# EDU_High-Speed-Design_CPU_DDR3.net
KiCad netlist of a schematic drawn in Altium Designer
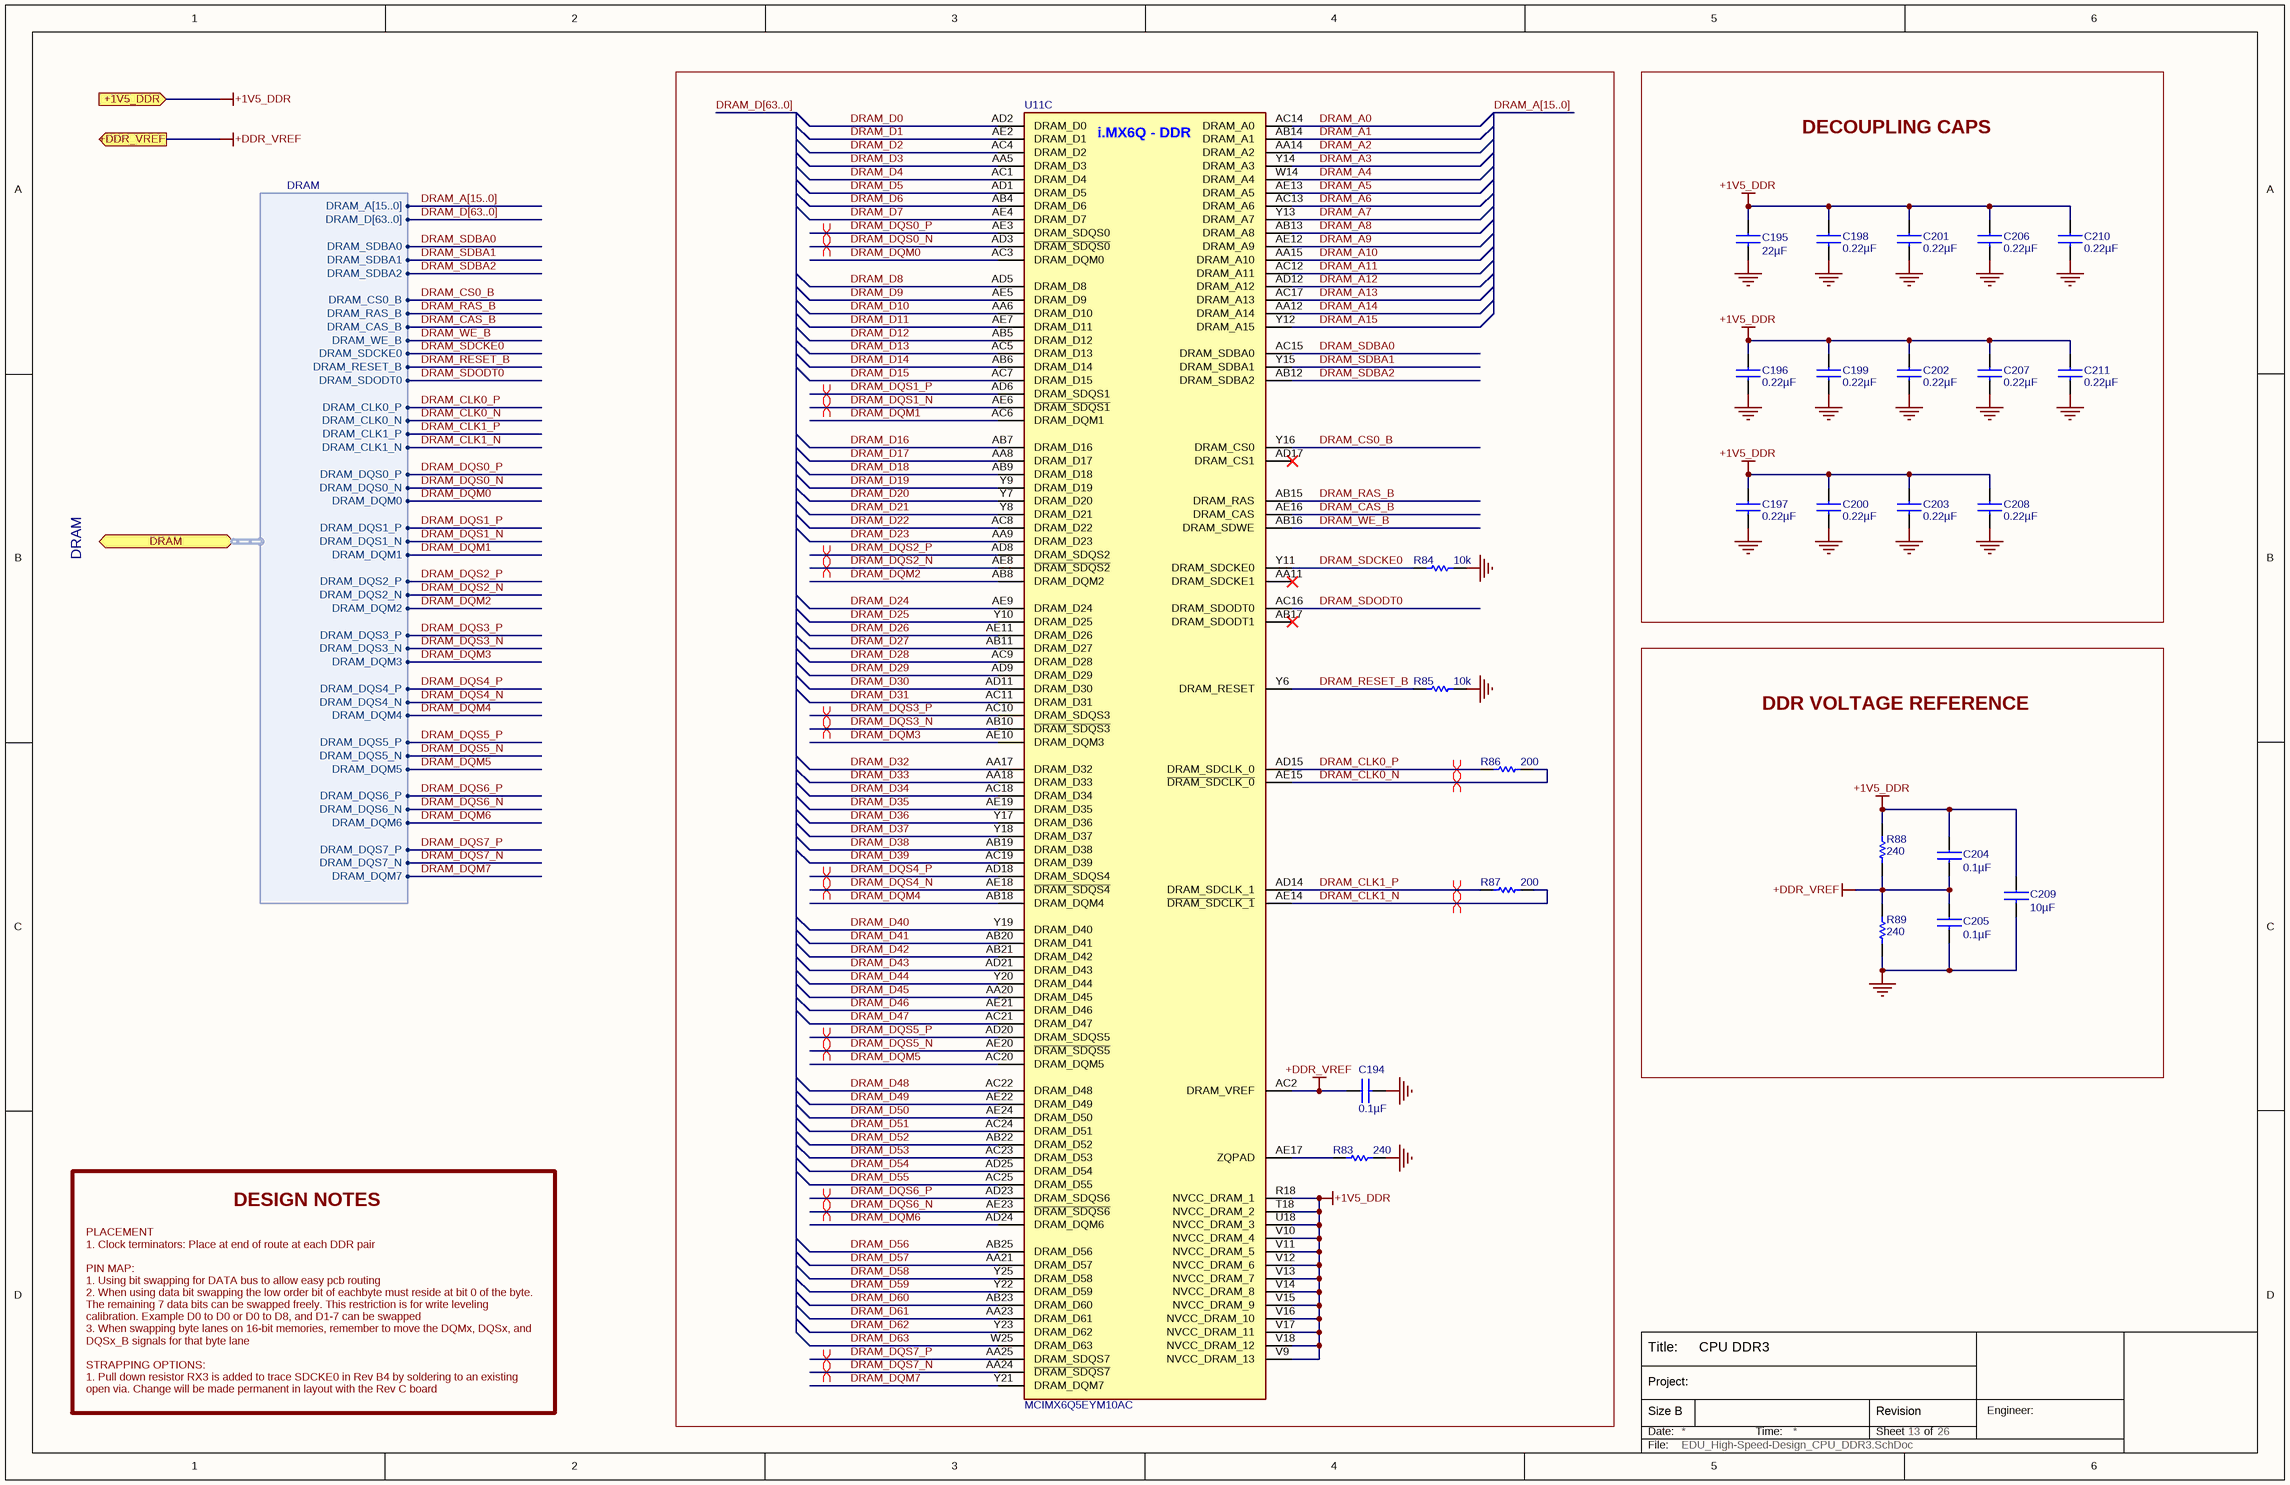
[diagram p0: EDU_High-Speed-Design_CPU_DDR3.SchDoc]

(export (version "E")
  (design (tool "Eeschema 10.0.6"))
  (components
    (comp (ref "C194")
      (value "0.1µF")
      (footprint "C0402")
      (description "CAP CER .10UF 50V X5R 10% 0402")
      (fields (field (name "VOLTAGE") "50V"))
      (libsource (lib "EDU_High-Speed-Design") (part "C1005X5R1H104K"))
    )
    (comp (ref "C195")
      (value "22µF")
      (footprint "C0603")
      (description "CAP CER 22UF 4V 20% X5R 0603")
      (fields (field (name "VOLTAGE") "4V"))
      (libsource (lib "EDU_High-Speed-Design") (part "GRM188R60G226MEA0L"))
    )
    (comp (ref "C196")
      (value "0.22µF")
      (footprint "C0402")
      (description "CAP CER .22UF 25V X5R 20% 0402")
      (fields (field (name "VOLTAGE") "25V"))
      (libsource (lib "EDU_High-Speed-Design") (part "C1005X5R1E224M"))
    )
    (comp (ref "C197")
      (value "0.22µF")
      (footprint "C0402")
      (description "CAP CER .22UF 25V X5R 20% 0402")
      (fields (field (name "VOLTAGE") "25V"))
      (libsource (lib "EDU_High-Speed-Design") (part "C1005X5R1E224M"))
    )
    (comp (ref "C198")
      (value "0.22µF")
      (footprint "C0402")
      (description "CAP CER .22UF 25V X5R 20% 0402")
      (fields (field (name "VOLTAGE") "25V"))
      (libsource (lib "EDU_High-Speed-Design") (part "C1005X5R1E224M"))
    )
    (comp (ref "C199")
      (value "0.22µF")
      (footprint "C0402")
      (description "CAP CER .22UF 25V X5R 20% 0402")
      (fields (field (name "VOLTAGE") "25V"))
      (libsource (lib "EDU_High-Speed-Design") (part "C1005X5R1E224M"))
    )
    (comp (ref "C200")
      (value "0.22µF")
      (footprint "C0402")
      (description "CAP CER .22UF 25V X5R 20% 0402")
      (fields (field (name "VOLTAGE") "25V"))
      (libsource (lib "EDU_High-Speed-Design") (part "C1005X5R1E224M"))
    )
    (comp (ref "C201")
      (value "0.22µF")
      (footprint "C0402")
      (description "CAP CER .22UF 25V X5R 20% 0402")
      (fields (field (name "VOLTAGE") "25V"))
      (libsource (lib "EDU_High-Speed-Design") (part "C1005X5R1E224M"))
    )
    (comp (ref "C202")
      (value "0.22µF")
      (footprint "C0402")
      (description "CAP CER .22UF 25V X5R 20% 0402")
      (fields (field (name "VOLTAGE") "25V"))
      (libsource (lib "EDU_High-Speed-Design") (part "C1005X5R1E224M"))
    )
    (comp (ref "C203")
      (value "0.22µF")
      (footprint "C0402")
      (description "CAP CER .22UF 25V X5R 20% 0402")
      (fields (field (name "VOLTAGE") "25V"))
      (libsource (lib "EDU_High-Speed-Design") (part "C1005X5R1E224M"))
    )
    (comp (ref "C204")
      (value "0.1µF")
      (footprint "C0402")
      (description "CAP CER .10UF 50V X5R 10% 0402")
      (fields (field (name "VOLTAGE") "50V"))
      (libsource (lib "EDU_High-Speed-Design") (part "C1005X5R1H104K"))
    )
    (comp (ref "C205")
      (value "0.1µF")
      (footprint "C0402")
      (description "CAP CER .10UF 50V X5R 10% 0402")
      (fields (field (name "VOLTAGE") "50V"))
      (libsource (lib "EDU_High-Speed-Design") (part "C1005X5R1H104K"))
    )
    (comp (ref "C206")
      (value "0.22µF")
      (footprint "C0402")
      (description "CAP CER .22UF 25V X5R 20% 0402")
      (fields (field (name "VOLTAGE") "25V"))
      (libsource (lib "EDU_High-Speed-Design") (part "C1005X5R1E224M"))
    )
    (comp (ref "C207")
      (value "0.22µF")
      (footprint "C0402")
      (description "CAP CER .22UF 25V X5R 20% 0402")
      (fields (field (name "VOLTAGE") "25V"))
      (libsource (lib "EDU_High-Speed-Design") (part "C1005X5R1E224M"))
    )
    (comp (ref "C208")
      (value "0.22µF")
      (footprint "C0402")
      (description "CAP CER .22UF 25V X5R 20% 0402")
      (fields (field (name "VOLTAGE") "25V"))
      (libsource (lib "EDU_High-Speed-Design") (part "C1005X5R1E224M"))
    )
    (comp (ref "C209")
      (value "10µF")
      (footprint "C0603")
      (description "CAP CER 10UF 6.3V X5R 20% 0603")
      (fields (field (name "VOLTAGE") "6.3V"))
      (libsource (lib "EDU_High-Speed-Design") (part "C1608X5R0J106M"))
    )
    (comp (ref "C210")
      (value "0.22µF")
      (footprint "C0402")
      (description "CAP CER .22UF 25V X5R 20% 0402")
      (fields (field (name "VOLTAGE") "25V"))
      (libsource (lib "EDU_High-Speed-Design") (part "C1005X5R1E224M"))
    )
    (comp (ref "C211")
      (value "0.22µF")
      (footprint "C0402")
      (description "CAP CER .22UF 25V X5R 20% 0402")
      (fields (field (name "VOLTAGE") "25V"))
      (libsource (lib "EDU_High-Speed-Design") (part "C1005X5R1E224M"))
    )
    (comp (ref "R83")
      (value "240")
      (footprint "R0402")
      (description "RES TF 240 OHM 1% 0.0625W 0402")
      (libsource (lib "EDU_High-Speed-Design") (part "RMCF0402FT240R"))
    )
    (comp (ref "R84")
      (value "10k")
      (footprint "R0402")
      (description "RES 10.0K OHM 1/16W 1% 0402 SMD")
      (libsource (lib "EDU_High-Speed-Design") (part "RC0402FR-0710KL"))
    )
    (comp (ref "R85")
      (value "10k")
      (footprint "R0402")
      (description "RES 10.0K OHM 1/16W 1% 0402 SMD")
      (libsource (lib "EDU_High-Speed-Design") (part "RC0402FR-0710KL"))
    )
    (comp (ref "R86")
      (value "200")
      (footprint "R0402")
      (description "RES 200 OHM 1/16W 1% 0402 SMD")
      (libsource (lib "EDU_High-Speed-Design") (part "CRCW0402200RFKED"))
    )
    (comp (ref "R87")
      (value "200")
      (footprint "R0402")
      (description "RES 200 OHM 1/16W 1% 0402 SMD")
      (libsource (lib "EDU_High-Speed-Design") (part "CRCW0402200RFKED"))
    )
    (comp (ref "R88")
      (value "240")
      (footprint "R0402")
      (description "RES TF 240 OHM 1% 0.0625W 0402")
      (libsource (lib "EDU_High-Speed-Design") (part "RMCF0402FT240R"))
    )
    (comp (ref "R89")
      (value "240")
      (footprint "R0402")
      (description "RES TF 240 OHM 1% 0.0625W 0402")
      (libsource (lib "EDU_High-Speed-Design") (part "RMCF0402FT240R"))
    )
    (comp (ref "U11")
      (value "MCIMX6Q5EYM10AC")
      (footprint "MCIMX6Q5EYM10AC")
      (description "IC MCU 32BIT ARM QUAD 624FCBGA")
      (libsource (lib "EDU_High-Speed-Design") (part "MCIMX6Q5EYM10AC"))
    )
  )
  (nets
    (net (code "2") (name "+1V5_DDR") (class "Default")
      (node (ref "C195") (pin "1") (pinfunction "1_1") (pintype "passive"))
      (node (ref "C196") (pin "1") (pinfunction "1_1") (pintype "passive"))
      (node (ref "C197") (pin "1") (pinfunction "1_1") (pintype "passive"))
      (node (ref "C198") (pin "1") (pinfunction "1_1") (pintype "passive"))
      (node (ref "C199") (pin "1") (pinfunction "1_1") (pintype "passive"))
      (node (ref "C200") (pin "1") (pinfunction "1_1") (pintype "passive"))
      (node (ref "C201") (pin "1") (pinfunction "1_1") (pintype "passive"))
      (node (ref "C202") (pin "1") (pinfunction "1_1") (pintype "passive"))
      (node (ref "C203") (pin "1") (pinfunction "1_1") (pintype "passive"))
      (node (ref "C204") (pin "1") (pinfunction "1_1") (pintype "passive"))
      (node (ref "C206") (pin "1") (pinfunction "1_1") (pintype "passive"))
      (node (ref "C207") (pin "1") (pinfunction "1_1") (pintype "passive"))
      (node (ref "C208") (pin "1") (pinfunction "1_1") (pintype "passive"))
      (node (ref "C209") (pin "1") (pinfunction "1_1") (pintype "passive"))
      (node (ref "C210") (pin "1") (pinfunction "1_1") (pintype "passive"))
      (node (ref "C211") (pin "1") (pinfunction "1_1") (pintype "passive"))
      (node (ref "R88") (pin "1") (pinfunction "1_1") (pintype "passive"))
      (node (ref "U11") (pin "R18") (pinfunction "NVCC_DRAM_1_R18") (pintype "passive"))
      (node (ref "U11") (pin "T18") (pinfunction "NVCC_DRAM_2_T18") (pintype "passive"))
      (node (ref "U11") (pin "U18") (pinfunction "NVCC_DRAM_3_U18") (pintype "passive"))
      (node (ref "U11") (pin "V10") (pinfunction "NVCC_DRAM_4_V10") (pintype "passive"))
      (node (ref "U11") (pin "V11") (pinfunction "NVCC_DRAM_5_V11") (pintype "passive"))
      (node (ref "U11") (pin "V12") (pinfunction "NVCC_DRAM_6_V12") (pintype "passive"))
      (node (ref "U11") (pin "V13") (pinfunction "NVCC_DRAM_7_V13") (pintype "passive"))
      (node (ref "U11") (pin "V14") (pinfunction "NVCC_DRAM_8_V14") (pintype "passive"))
      (node (ref "U11") (pin "V15") (pinfunction "NVCC_DRAM_9_V15") (pintype "passive"))
      (node (ref "U11") (pin "V16") (pinfunction "NVCC_DRAM_10_V16") (pintype "passive"))
      (node (ref "U11") (pin "V17") (pinfunction "NVCC_DRAM_11_V17") (pintype "passive"))
      (node (ref "U11") (pin "V18") (pinfunction "NVCC_DRAM_12_V18") (pintype "passive"))
      (node (ref "U11") (pin "V9") (pinfunction "NVCC_DRAM_13_V9") (pintype "passive"))
    )
    (net (code "3") (name "+DDR_VREF") (class "Default")
      (node (ref "C194") (pin "1") (pinfunction "1_1") (pintype "passive"))
      (node (ref "C204") (pin "2") (pinfunction "2_2") (pintype "passive"))
      (node (ref "C205") (pin "1") (pinfunction "1_1") (pintype "passive"))
      (node (ref "R88") (pin "2") (pinfunction "2_2") (pintype "passive"))
      (node (ref "R89") (pin "1") (pinfunction "1_1") (pintype "passive"))
      (node (ref "U11") (pin "AC2") (pinfunction "DRAM_VREF_AC2") (pintype "passive"))
    )
    (net (code "4") (name "/DRAM_A0") (class "Default")
      (node (ref "U11") (pin "AC14") (pinfunction "DRAM_A0_AC14") (pintype "passive"))
    )
    (net (code "5") (name "/DRAM_A1") (class "Default")
      (node (ref "U11") (pin "AB14") (pinfunction "DRAM_A1_AB14") (pintype "passive"))
    )
    (net (code "6") (name "/DRAM_A2") (class "Default")
      (node (ref "U11") (pin "AA14") (pinfunction "DRAM_A2_AA14") (pintype "passive"))
    )
    (net (code "7") (name "/DRAM_A3") (class "Default")
      (node (ref "U11") (pin "Y14") (pinfunction "DRAM_A3_Y14") (pintype "passive"))
    )
    (net (code "8") (name "/DRAM_A4") (class "Default")
      (node (ref "U11") (pin "W14") (pinfunction "DRAM_A4_W14") (pintype "passive"))
    )
    (net (code "9") (name "/DRAM_A5") (class "Default")
      (node (ref "U11") (pin "AE13") (pinfunction "DRAM_A5_AE13") (pintype "passive"))
    )
    (net (code "10") (name "/DRAM_A6") (class "Default")
      (node (ref "U11") (pin "AC13") (pinfunction "DRAM_A6_AC13") (pintype "passive"))
    )
    (net (code "11") (name "/DRAM_A7") (class "Default")
      (node (ref "U11") (pin "Y13") (pinfunction "DRAM_A7_Y13") (pintype "passive"))
    )
    (net (code "12") (name "/DRAM_A8") (class "Default")
      (node (ref "U11") (pin "AB13") (pinfunction "DRAM_A8_AB13") (pintype "passive"))
    )
    (net (code "13") (name "/DRAM_A9") (class "Default")
      (node (ref "U11") (pin "AE12") (pinfunction "DRAM_A9_AE12") (pintype "passive"))
    )
    (net (code "14") (name "/DRAM_A10") (class "Default")
      (node (ref "U11") (pin "AA15") (pinfunction "DRAM_A10_AA15") (pintype "passive"))
    )
    (net (code "15") (name "/DRAM_A11") (class "Default")
      (node (ref "U11") (pin "AC12") (pinfunction "DRAM_A11_AC12") (pintype "passive"))
    )
    (net (code "16") (name "/DRAM_A12") (class "Default")
      (node (ref "U11") (pin "AD12") (pinfunction "DRAM_A12_AD12") (pintype "passive"))
    )
    (net (code "17") (name "/DRAM_A13") (class "Default")
      (node (ref "U11") (pin "AC17") (pinfunction "DRAM_A13_AC17") (pintype "passive"))
    )
    (net (code "18") (name "/DRAM_A14") (class "Default")
      (node (ref "U11") (pin "AA12") (pinfunction "DRAM_A14_AA12") (pintype "passive"))
    )
    (net (code "19") (name "/DRAM_A15") (class "Default")
      (node (ref "U11") (pin "Y12") (pinfunction "DRAM_A15_Y12") (pintype "passive"))
    )
    (net (code "21") (name "/DRAM_CAS_B") (class "Default")
      (node (ref "U11") (pin "AE16") (pinfunction "DRAM_CAS_AE16") (pintype "passive"))
    )
    (net (code "22") (name "/DRAM_CLK0_N") (class "Default")
      (node (ref "R86") (pin "2") (pinfunction "2_2") (pintype "passive"))
      (node (ref "U11") (pin "AE15") (pinfunction "~{DRAM_SDCLK_0}_AE15") (pintype "passive"))
    )
    (net (code "23") (name "/DRAM_CLK0_P") (class "Default")
      (node (ref "R86") (pin "1") (pinfunction "1_1") (pintype "passive"))
      (node (ref "U11") (pin "AD15") (pinfunction "DRAM_SDCLK_0_AD15") (pintype "passive"))
    )
    (net (code "24") (name "/DRAM_CLK1_N") (class "Default")
      (node (ref "R87") (pin "2") (pinfunction "2_2") (pintype "passive"))
      (node (ref "U11") (pin "AE14") (pinfunction "~{DRAM_SDCLK_1}_AE14") (pintype "passive"))
    )
    (net (code "25") (name "/DRAM_CLK1_P") (class "Default")
      (node (ref "R87") (pin "1") (pinfunction "1_1") (pintype "passive"))
      (node (ref "U11") (pin "AD14") (pinfunction "DRAM_SDCLK_1_AD14") (pintype "passive"))
    )
    (net (code "26") (name "/DRAM_CS0_B") (class "Default")
      (node (ref "U11") (pin "Y16") (pinfunction "DRAM_CS0_Y16") (pintype "passive"))
    )
    (net (code "27") (name "/DRAM_D0") (class "Default")
      (node (ref "U11") (pin "AD2") (pinfunction "DRAM_D0_AD2") (pintype "passive"))
    )
    (net (code "28") (name "/DRAM_D1") (class "Default")
      (node (ref "U11") (pin "AE2") (pinfunction "DRAM_D1_AE2") (pintype "passive"))
    )
    (net (code "29") (name "/DRAM_D2") (class "Default")
      (node (ref "U11") (pin "AC4") (pinfunction "DRAM_D2_AC4") (pintype "passive"))
    )
    (net (code "30") (name "/DRAM_D3") (class "Default")
      (node (ref "U11") (pin "AA5") (pinfunction "DRAM_D3_AA5") (pintype "passive"))
    )
    (net (code "31") (name "/DRAM_D4") (class "Default")
      (node (ref "U11") (pin "AC1") (pinfunction "DRAM_D4_AC1") (pintype "passive"))
    )
    (net (code "32") (name "/DRAM_D5") (class "Default")
      (node (ref "U11") (pin "AD1") (pinfunction "DRAM_D5_AD1") (pintype "passive"))
    )
    (net (code "33") (name "/DRAM_D6") (class "Default")
      (node (ref "U11") (pin "AB4") (pinfunction "DRAM_D6_AB4") (pintype "passive"))
    )
    (net (code "34") (name "/DRAM_D7") (class "Default")
      (node (ref "U11") (pin "AE4") (pinfunction "DRAM_D7_AE4") (pintype "passive"))
    )
    (net (code "35") (name "/DRAM_D8") (class "Default")
      (node (ref "U11") (pin "AD5") (pinfunction "DRAM_D8_AD5") (pintype "passive"))
    )
    (net (code "36") (name "/DRAM_D9") (class "Default")
      (node (ref "U11") (pin "AE5") (pinfunction "DRAM_D9_AE5") (pintype "passive"))
    )
    (net (code "37") (name "/DRAM_D10") (class "Default")
      (node (ref "U11") (pin "AA6") (pinfunction "DRAM_D10_AA6") (pintype "passive"))
    )
    (net (code "38") (name "/DRAM_D11") (class "Default")
      (node (ref "U11") (pin "AE7") (pinfunction "DRAM_D11_AE7") (pintype "passive"))
    )
    (net (code "39") (name "/DRAM_D12") (class "Default")
      (node (ref "U11") (pin "AB5") (pinfunction "DRAM_D12_AB5") (pintype "passive"))
    )
    (net (code "40") (name "/DRAM_D13") (class "Default")
      (node (ref "U11") (pin "AC5") (pinfunction "DRAM_D13_AC5") (pintype "passive"))
    )
    (net (code "41") (name "/DRAM_D14") (class "Default")
      (node (ref "U11") (pin "AB6") (pinfunction "DRAM_D14_AB6") (pintype "passive"))
    )
    (net (code "42") (name "/DRAM_D15") (class "Default")
      (node (ref "U11") (pin "AC7") (pinfunction "DRAM_D15_AC7") (pintype "passive"))
    )
    (net (code "43") (name "/DRAM_D16") (class "Default")
      (node (ref "U11") (pin "AB7") (pinfunction "DRAM_D16_AB7") (pintype "passive"))
    )
    (net (code "44") (name "/DRAM_D17") (class "Default")
      (node (ref "U11") (pin "AA8") (pinfunction "DRAM_D17_AA8") (pintype "passive"))
    )
    (net (code "45") (name "/DRAM_D18") (class "Default")
      (node (ref "U11") (pin "AB9") (pinfunction "DRAM_D18_AB9") (pintype "passive"))
    )
    (net (code "46") (name "/DRAM_D19") (class "Default")
      (node (ref "U11") (pin "Y9") (pinfunction "DRAM_D19_Y9") (pintype "passive"))
    )
    (net (code "47") (name "/DRAM_D20") (class "Default")
      (node (ref "U11") (pin "Y7") (pinfunction "DRAM_D20_Y7") (pintype "passive"))
    )
    (net (code "48") (name "/DRAM_D21") (class "Default")
      (node (ref "U11") (pin "Y8") (pinfunction "DRAM_D21_Y8") (pintype "passive"))
    )
    (net (code "49") (name "/DRAM_D22") (class "Default")
      (node (ref "U11") (pin "AC8") (pinfunction "DRAM_D22_AC8") (pintype "passive"))
    )
    (net (code "50") (name "/DRAM_D23") (class "Default")
      (node (ref "U11") (pin "AA9") (pinfunction "DRAM_D23_AA9") (pintype "passive"))
    )
    (net (code "51") (name "/DRAM_D24") (class "Default")
      (node (ref "U11") (pin "AE9") (pinfunction "DRAM_D24_AE9") (pintype "passive"))
    )
    (net (code "52") (name "/DRAM_D25") (class "Default")
      (node (ref "U11") (pin "Y10") (pinfunction "DRAM_D25_Y10") (pintype "passive"))
    )
    (net (code "53") (name "/DRAM_D26") (class "Default")
      (node (ref "U11") (pin "AE11") (pinfunction "DRAM_D26_AE11") (pintype "passive"))
    )
    (net (code "54") (name "/DRAM_D27") (class "Default")
      (node (ref "U11") (pin "AB11") (pinfunction "DRAM_D27_AB11") (pintype "passive"))
    )
    (net (code "55") (name "/DRAM_D28") (class "Default")
      (node (ref "U11") (pin "AC9") (pinfunction "DRAM_D28_AC9") (pintype "passive"))
    )
    (net (code "56") (name "/DRAM_D29") (class "Default")
      (node (ref "U11") (pin "AD9") (pinfunction "DRAM_D29_AD9") (pintype "passive"))
    )
    (net (code "57") (name "/DRAM_D30") (class "Default")
      (node (ref "U11") (pin "AD11") (pinfunction "DRAM_D30_AD11") (pintype "passive"))
    )
    (net (code "58") (name "/DRAM_D31") (class "Default")
      (node (ref "U11") (pin "AC11") (pinfunction "DRAM_D31_AC11") (pintype "passive"))
    )
    (net (code "59") (name "/DRAM_D32") (class "Default")
      (node (ref "U11") (pin "AA17") (pinfunction "DRAM_D32_AA17") (pintype "passive"))
    )
    (net (code "60") (name "/DRAM_D33") (class "Default")
      (node (ref "U11") (pin "AA18") (pinfunction "DRAM_D33_AA18") (pintype "passive"))
    )
    (net (code "61") (name "/DRAM_D34") (class "Default")
      (node (ref "U11") (pin "AC18") (pinfunction "DRAM_D34_AC18") (pintype "passive"))
    )
    (net (code "62") (name "/DRAM_D35") (class "Default")
      (node (ref "U11") (pin "AE19") (pinfunction "DRAM_D35_AE19") (pintype "passive"))
    )
    (net (code "63") (name "/DRAM_D36") (class "Default")
      (node (ref "U11") (pin "Y17") (pinfunction "DRAM_D36_Y17") (pintype "passive"))
    )
    (net (code "64") (name "/DRAM_D37") (class "Default")
      (node (ref "U11") (pin "Y18") (pinfunction "DRAM_D37_Y18") (pintype "passive"))
    )
    (net (code "65") (name "/DRAM_D38") (class "Default")
      (node (ref "U11") (pin "AB19") (pinfunction "DRAM_D38_AB19") (pintype "passive"))
    )
    (net (code "66") (name "/DRAM_D39") (class "Default")
      (node (ref "U11") (pin "AC19") (pinfunction "DRAM_D39_AC19") (pintype "passive"))
    )
    (net (code "67") (name "/DRAM_D40") (class "Default")
      (node (ref "U11") (pin "Y19") (pinfunction "DRAM_D40_Y19") (pintype "passive"))
    )
    (net (code "68") (name "/DRAM_D41") (class "Default")
      (node (ref "U11") (pin "AB20") (pinfunction "DRAM_D41_AB20") (pintype "passive"))
    )
    (net (code "69") (name "/DRAM_D42") (class "Default")
      (node (ref "U11") (pin "AB21") (pinfunction "DRAM_D42_AB21") (pintype "passive"))
    )
    (net (code "70") (name "/DRAM_D43") (class "Default")
      (node (ref "U11") (pin "AD21") (pinfunction "DRAM_D43_AD21") (pintype "passive"))
    )
    (net (code "71") (name "/DRAM_D44") (class "Default")
      (node (ref "U11") (pin "Y20") (pinfunction "DRAM_D44_Y20") (pintype "passive"))
    )
    (net (code "72") (name "/DRAM_D45") (class "Default")
      (node (ref "U11") (pin "AA20") (pinfunction "DRAM_D45_AA20") (pintype "passive"))
    )
    (net (code "73") (name "/DRAM_D46") (class "Default")
      (node (ref "U11") (pin "AE21") (pinfunction "DRAM_D46_AE21") (pintype "passive"))
    )
    (net (code "74") (name "/DRAM_D47") (class "Default")
      (node (ref "U11") (pin "AC21") (pinfunction "DRAM_D47_AC21") (pintype "passive"))
    )
    (net (code "75") (name "/DRAM_D48") (class "Default")
      (node (ref "U11") (pin "AC22") (pinfunction "DRAM_D48_AC22") (pintype "passive"))
    )
    (net (code "76") (name "/DRAM_D49") (class "Default")
      (node (ref "U11") (pin "AE22") (pinfunction "DRAM_D49_AE22") (pintype "passive"))
    )
    (net (code "77") (name "/DRAM_D50") (class "Default")
      (node (ref "U11") (pin "AE24") (pinfunction "DRAM_D50_AE24") (pintype "passive"))
    )
    (net (code "78") (name "/DRAM_D51") (class "Default")
      (node (ref "U11") (pin "AC24") (pinfunction "DRAM_D51_AC24") (pintype "passive"))
    )
    (net (code "79") (name "/DRAM_D52") (class "Default")
      (node (ref "U11") (pin "AB22") (pinfunction "DRAM_D52_AB22") (pintype "passive"))
    )
    (net (code "80") (name "/DRAM_D53") (class "Default")
      (node (ref "U11") (pin "AC23") (pinfunction "DRAM_D53_AC23") (pintype "passive"))
    )
    (net (code "81") (name "/DRAM_D54") (class "Default")
      (node (ref "U11") (pin "AD25") (pinfunction "DRAM_D54_AD25") (pintype "passive"))
    )
    (net (code "82") (name "/DRAM_D55") (class "Default")
      (node (ref "U11") (pin "AC25") (pinfunction "DRAM_D55_AC25") (pintype "passive"))
    )
    (net (code "83") (name "/DRAM_D56") (class "Default")
      (node (ref "U11") (pin "AB25") (pinfunction "DRAM_D56_AB25") (pintype "passive"))
    )
    (net (code "84") (name "/DRAM_D57") (class "Default")
      (node (ref "U11") (pin "AA21") (pinfunction "DRAM_D57_AA21") (pintype "passive"))
    )
    (net (code "85") (name "/DRAM_D58") (class "Default")
      (node (ref "U11") (pin "Y25") (pinfunction "DRAM_D58_Y25") (pintype "passive"))
    )
    (net (code "86") (name "/DRAM_D59") (class "Default")
      (node (ref "U11") (pin "Y22") (pinfunction "DRAM_D59_Y22") (pintype "passive"))
    )
    (net (code "87") (name "/DRAM_D60") (class "Default")
      (node (ref "U11") (pin "AB23") (pinfunction "DRAM_D60_AB23") (pintype "passive"))
    )
    (net (code "88") (name "/DRAM_D61") (class "Default")
      (node (ref "U11") (pin "AA23") (pinfunction "DRAM_D61_AA23") (pintype "passive"))
    )
    (net (code "89") (name "/DRAM_D62") (class "Default")
      (node (ref "U11") (pin "Y23") (pinfunction "DRAM_D62_Y23") (pintype "passive"))
    )
    (net (code "90") (name "/DRAM_D63") (class "Default")
      (node (ref "U11") (pin "W25") (pinfunction "DRAM_D63_W25") (pintype "passive"))
    )
    (net (code "91") (name "/DRAM_DQM0") (class "Default")
      (node (ref "U11") (pin "AC3") (pinfunction "DRAM_DQM0_AC3") (pintype "passive"))
    )
    (net (code "92") (name "/DRAM_DQM1") (class "Default")
      (node (ref "U11") (pin "AC6") (pinfunction "DRAM_DQM1_AC6") (pintype "passive"))
    )
    (net (code "93") (name "/DRAM_DQM2") (class "Default")
      (node (ref "U11") (pin "AB8") (pinfunction "DRAM_DQM2_AB8") (pintype "passive"))
    )
    (net (code "94") (name "/DRAM_DQM3") (class "Default")
      (node (ref "U11") (pin "AE10") (pinfunction "DRAM_DQM3_AE10") (pintype "passive"))
    )
    (net (code "95") (name "/DRAM_DQM4") (class "Default")
      (node (ref "U11") (pin "AB18") (pinfunction "DRAM_DQM4_AB18") (pintype "passive"))
    )
    (net (code "96") (name "/DRAM_DQM5") (class "Default")
      (node (ref "U11") (pin "AC20") (pinfunction "DRAM_DQM5_AC20") (pintype "passive"))
    )
    (net (code "97") (name "/DRAM_DQM6") (class "Default")
      (node (ref "U11") (pin "AD24") (pinfunction "DRAM_DQM6_AD24") (pintype "passive"))
    )
    (net (code "98") (name "/DRAM_DQM7") (class "Default")
      (node (ref "U11") (pin "Y21") (pinfunction "DRAM_DQM7_Y21") (pintype "passive"))
    )
    (net (code "99") (name "/DRAM_DQS0_N") (class "Default")
      (node (ref "U11") (pin "AD3") (pinfunction "~{DRAM_SDQS0}_AD3") (pintype "passive"))
    )
    (net (code "100") (name "/DRAM_DQS0_P") (class "Default")
      (node (ref "U11") (pin "AE3") (pinfunction "DRAM_SDQS0_AE3") (pintype "passive"))
    )
    (net (code "101") (name "/DRAM_DQS1_N") (class "Default")
      (node (ref "U11") (pin "AE6") (pinfunction "~{DRAM_SDQS1}_AE6") (pintype "passive"))
    )
    (net (code "102") (name "/DRAM_DQS1_P") (class "Default")
      (node (ref "U11") (pin "AD6") (pinfunction "DRAM_SDQS1_AD6") (pintype "passive"))
    )
    (net (code "103") (name "/DRAM_DQS2_N") (class "Default")
      (node (ref "U11") (pin "AE8") (pinfunction "~{DRAM_SDQS2}_AE8") (pintype "passive"))
    )
    (net (code "104") (name "/DRAM_DQS2_P") (class "Default")
      (node (ref "U11") (pin "AD8") (pinfunction "DRAM_SDQS2_AD8") (pintype "passive"))
    )
    (net (code "105") (name "/DRAM_DQS3_N") (class "Default")
      (node (ref "U11") (pin "AB10") (pinfunction "~{DRAM_SDQS3}_AB10") (pintype "passive"))
    )
    (net (code "106") (name "/DRAM_DQS3_P") (class "Default")
      (node (ref "U11") (pin "AC10") (pinfunction "DRAM_SDQS3_AC10") (pintype "passive"))
    )
    (net (code "107") (name "/DRAM_DQS4_N") (class "Default")
      (node (ref "U11") (pin "AE18") (pinfunction "~{DRAM_SDQS4}_AE18") (pintype "passive"))
    )
    (net (code "108") (name "/DRAM_DQS4_P") (class "Default")
      (node (ref "U11") (pin "AD18") (pinfunction "DRAM_SDQS4_AD18") (pintype "passive"))
    )
    (net (code "109") (name "/DRAM_DQS5_N") (class "Default")
      (node (ref "U11") (pin "AE20") (pinfunction "~{DRAM_SDQS5}_AE20") (pintype "passive"))
    )
    (net (code "110") (name "/DRAM_DQS5_P") (class "Default")
      (node (ref "U11") (pin "AD20") (pinfunction "DRAM_SDQS5_AD20") (pintype "passive"))
    )
    (net (code "111") (name "/DRAM_DQS6_N") (class "Default")
      (node (ref "U11") (pin "AE23") (pinfunction "~{DRAM_SDQS6}_AE23") (pintype "passive"))
    )
    (net (code "112") (name "/DRAM_DQS6_P") (class "Default")
      (node (ref "U11") (pin "AD23") (pinfunction "DRAM_SDQS6_AD23") (pintype "passive"))
    )
    (net (code "113") (name "/DRAM_DQS7_N") (class "Default")
      (node (ref "U11") (pin "AA24") (pinfunction "~{DRAM_SDQS7}_AA24") (pintype "passive"))
    )
    (net (code "114") (name "/DRAM_DQS7_P") (class "Default")
      (node (ref "U11") (pin "AA25") (pinfunction "DRAM_SDQS7_AA25") (pintype "passive"))
    )
    (net (code "116") (name "/DRAM_RAS_B") (class "Default")
      (node (ref "U11") (pin "AB15") (pinfunction "DRAM_RAS_AB15") (pintype "passive"))
    )
    (net (code "117") (name "/DRAM_RESET_B") (class "Default")
      (node (ref "R85") (pin "1") (pinfunction "1_1") (pintype "passive"))
      (node (ref "U11") (pin "Y6") (pinfunction "DRAM_RESET_Y6") (pintype "passive"))
    )
    (net (code "118") (name "/DRAM_SDBA0") (class "Default")
      (node (ref "U11") (pin "AC15") (pinfunction "DRAM_SDBA0_AC15") (pintype "passive"))
    )
    (net (code "119") (name "/DRAM_SDBA1") (class "Default")
      (node (ref "U11") (pin "Y15") (pinfunction "DRAM_SDBA1_Y15") (pintype "passive"))
    )
    (net (code "120") (name "/DRAM_SDBA2") (class "Default")
      (node (ref "U11") (pin "AB12") (pinfunction "DRAM_SDBA2_AB12") (pintype "passive"))
    )
    (net (code "121") (name "/DRAM_SDCKE0") (class "Default")
      (node (ref "R84") (pin "1") (pinfunction "1_1") (pintype "passive"))
      (node (ref "U11") (pin "Y11") (pinfunction "DRAM_SDCKE0_Y11") (pintype "passive"))
    )
    (net (code "122") (name "/DRAM_SDODT0") (class "Default")
      (node (ref "U11") (pin "AC16") (pinfunction "DRAM_SDODT0_AC16") (pintype "passive"))
    )
    (net (code "123") (name "/DRAM_WE_B") (class "Default")
      (node (ref "U11") (pin "AB16") (pinfunction "DRAM_SDWE_AB16") (pintype "passive"))
    )
    (net (code "125") (name "GND") (class "Default")
      (node (ref "C194") (pin "2") (pinfunction "2_2") (pintype "passive"))
      (node (ref "C195") (pin "2") (pinfunction "2_2") (pintype "passive"))
      (node (ref "C196") (pin "2") (pinfunction "2_2") (pintype "passive"))
      (node (ref "C197") (pin "2") (pinfunction "2_2") (pintype "passive"))
      (node (ref "C198") (pin "2") (pinfunction "2_2") (pintype "passive"))
      (node (ref "C199") (pin "2") (pinfunction "2_2") (pintype "passive"))
      (node (ref "C200") (pin "2") (pinfunction "2_2") (pintype "passive"))
      (node (ref "C201") (pin "2") (pinfunction "2_2") (pintype "passive"))
      (node (ref "C202") (pin "2") (pinfunction "2_2") (pintype "passive"))
      (node (ref "C203") (pin "2") (pinfunction "2_2") (pintype "passive"))
      (node (ref "C205") (pin "2") (pinfunction "2_2") (pintype "passive"))
      (node (ref "C206") (pin "2") (pinfunction "2_2") (pintype "passive"))
      (node (ref "C207") (pin "2") (pinfunction "2_2") (pintype "passive"))
      (node (ref "C208") (pin "2") (pinfunction "2_2") (pintype "passive"))
      (node (ref "C209") (pin "2") (pinfunction "2_2") (pintype "passive"))
      (node (ref "C210") (pin "2") (pinfunction "2_2") (pintype "passive"))
      (node (ref "C211") (pin "2") (pinfunction "2_2") (pintype "passive"))
      (node (ref "R83") (pin "1") (pinfunction "1_1") (pintype "passive"))
      (node (ref "R84") (pin "2") (pinfunction "2_2") (pintype "passive"))
      (node (ref "R85") (pin "2") (pinfunction "2_2") (pintype "passive"))
      (node (ref "R89") (pin "2") (pinfunction "2_2") (pintype "passive"))
    )
    (net (code "126") (name "Net-(U11C-ZQPAD)") (class "Default")
      (node (ref "R83") (pin "2") (pinfunction "2_2") (pintype "passive"))
      (node (ref "U11") (pin "AE17") (pinfunction "ZQPAD_AE17") (pintype "passive"))
    )
    (net (code "127") (name "unconnected-(U11C-DRAM_CS1-PadAD17)") (class "Default")
      (node (ref "U11") (pin "AD17") (pinfunction "DRAM_CS1_AD17") (pintype "passive+no_connect"))
    )
    (net (code "128") (name "unconnected-(U11C-DRAM_SDCKE1-PadAA11)") (class "Default")
      (node (ref "U11") (pin "AA11") (pinfunction "DRAM_SDCKE1_AA11") (pintype "passive+no_connect"))
    )
    (net (code "129") (name "unconnected-(U11C-DRAM_SDODT1-PadAB17)") (class "Default")
      (node (ref "U11") (pin "AB17") (pinfunction "DRAM_SDODT1_AB17") (pintype "passive+no_connect"))
    )
  )
)
